# 3V3_LDO_1A.net
KiCad netlist of a schematic drawn in Altium Designer
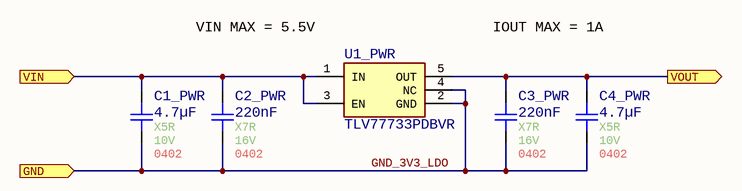
[diagram p0: 3V3_LDO_1A.SchDoc]

(export (version "E")
  (design (tool "Eeschema 10.0.6"))
  (components
    (comp (ref "C1_PWR")
      (value "4.7µF")
      (footprint "Generic 0402 capacitor")
      (fields
        (field (name "TEMPERATURE COEFFICIENT") "X5R")
        (field (name "VOLTAGE RATING") "10V")
        (field (name "CASE/PACKAGE") "0402")
        (field (name "TOLERANCE") "0%")
        (field (name "Comment") "GRT155R61A475ME13D")
      )
      (libsource (lib "Raise Robotics") (part "Unpolarized Capacitor"))
    )
    (comp (ref "C2_PWR")
      (value "220nF")
      (footprint "Generic 0402 capacitor")
      (fields
        (field (name "TEMPERATURE COEFFICIENT") "X7R")
        (field (name "VOLTAGE RATING") "16V")
        (field (name "CASE/PACKAGE") "0402")
        (field (name "TOLERANCE") "20%")
        (field (name "Comment") "GCM155R71C224ME02D")
      )
      (libsource (lib "Raise Robotics") (part "Unpolarized Capacitor"))
    )
    (comp (ref "C3_PWR")
      (value "220nF")
      (footprint "Generic 0402 capacitor")
      (fields
        (field (name "TEMPERATURE COEFFICIENT") "X7R")
        (field (name "VOLTAGE RATING") "16V")
        (field (name "CASE/PACKAGE") "0402")
        (field (name "TOLERANCE") "20%")
        (field (name "Comment") "GCM155R71C224ME02D")
      )
      (libsource (lib "Raise Robotics") (part "Unpolarized Capacitor"))
    )
    (comp (ref "C4_PWR")
      (value "4.7µF")
      (footprint "Generic 0402 capacitor")
      (fields
        (field (name "TEMPERATURE COEFFICIENT") "X5R")
        (field (name "VOLTAGE RATING") "10V")
        (field (name "CASE/PACKAGE") "0402")
        (field (name "TOLERANCE") "0%")
        (field (name "Comment") "GRT155R61A475ME13D")
      )
      (libsource (lib "Raise Robotics") (part "Unpolarized Capacitor"))
    )
    (comp (ref "U1_PWR")
      (value "TLV77733PDBVR")
      (footprint "SOT23-3_3x5x1.1mm_P0.95mm")
      (description "1A small-size high-PSRR low-dropout (LDO) regulator with enable 5-SOT-23 -40 to 125")
      (libsource (lib "Raise Robotics") (part "TI SOT23-5 LDO"))
    )
  )
  (nets
    (net (code "1") (name "/GND_3V3_LDO") (class "Default")
      (node (ref "C1_PWR") (pin "1") (pinfunction "1_1") (pintype "passive"))
      (node (ref "C2_PWR") (pin "1") (pinfunction "1_1") (pintype "passive"))
      (node (ref "C3_PWR") (pin "1") (pinfunction "1_1") (pintype "passive"))
      (node (ref "C4_PWR") (pin "1") (pinfunction "1_1") (pintype "passive"))
      (node (ref "U1_PWR") (pin "2") (pinfunction "GND_2") (pintype "passive"))
      (node (ref "U1_PWR") (pin "4") (pinfunction "NC_4") (pintype "passive"))
    )
    (net (code "2") (name "/VIN") (class "Default")
      (node (ref "C1_PWR") (pin "2") (pinfunction "2_2") (pintype "passive"))
      (node (ref "C2_PWR") (pin "2") (pinfunction "2_2") (pintype "passive"))
      (node (ref "U1_PWR") (pin "1") (pinfunction "IN_1") (pintype "passive"))
      (node (ref "U1_PWR") (pin "3") (pinfunction "EN_3") (pintype "passive"))
    )
    (net (code "3") (name "/VOUT") (class "Default")
      (node (ref "C3_PWR") (pin "2") (pinfunction "2_2") (pintype "passive"))
      (node (ref "C4_PWR") (pin "2") (pinfunction "2_2") (pintype "passive"))
      (node (ref "U1_PWR") (pin "5") (pinfunction "OUT_5") (pintype "passive"))
    )
  )
)
